# Rotary_Encoder.net
KiCad netlist of a schematic drawn in Altium Designer
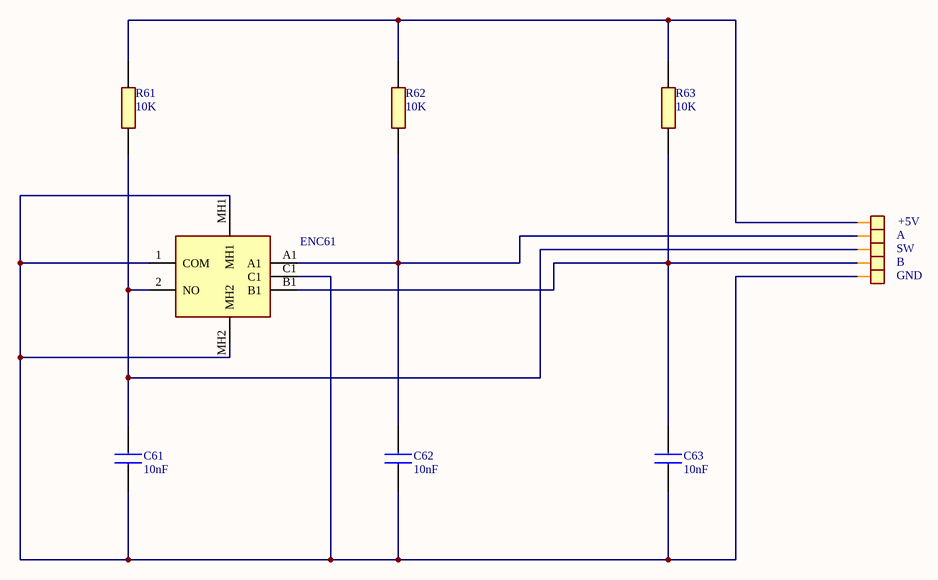
[diagram p0: Rotary_Encoder.SchDoc]

(export (version "E")
  (design (tool "Eeschema 10.0.6"))
  (components
    (comp (ref "C61")
      (value "10nF")
      (footprint "C315C103K5R5TA7303")
      (fields
        (field (name "MOUSER PART NUMBER") "80-C315C103K5R-TR")
        (field (name "MANUFACTURER_PART_NUMBER") "C315C103K5R5TA7303")
      )
      (libsource (lib "Master") (part "C315C103K5R5TA7303"))
    )
    (comp (ref "C62")
      (value "10nF")
      (footprint "C315C103K5R5TA7303")
      (fields
        (field (name "MOUSER PART NUMBER") "80-C315C103K5R-TR")
        (field (name "MANUFACTURER_PART_NUMBER") "C315C103K5R5TA7303")
      )
      (libsource (lib "Master") (part "C315C103K5R5TA7303"))
    )
    (comp (ref "C63")
      (value "10nF")
      (footprint "C315C103K5R5TA7303")
      (fields
        (field (name "MOUSER PART NUMBER") "80-C315C103K5R-TR")
        (field (name "MANUFACTURER_PART_NUMBER") "C315C103K5R5TA7303")
      )
      (libsource (lib "Master") (part "C315C103K5R5TA7303"))
    )
    (comp (ref "ENC61")
      (value "ROTARY&SWITCH")
      (footprint "Master:PEC11R4225FS0012")
      (description "Encoder 20mm SHAFT w/SWITCH")
      (fields
        (field (name "MANUFACTURER_PART_NUMBER") "PEC11R-4225F-S0012")
        (field (name "MOUSER PART NUMBER") "652-PEC11R-4225F-S12")
      )
      (libsource (lib "Master") (part "ROTARY"))
    )
    (comp (ref "H61") (value "+5V") (footprint "Header_M_S") (libsource (lib "Master") (part "Head_M_S")))
    (comp (ref "H62") (value "A") (footprint "Header_M_S") (libsource (lib "Master") (part "Head_M_S")))
    (comp (ref "H63") (value "SW") (footprint "Header_M_S") (libsource (lib "Master") (part "Head_M_S")))
    (comp (ref "H64") (value "B") (footprint "Header_M_S") (libsource (lib "Master") (part "Head_M_S")))
    (comp (ref "H65") (value "GND") (footprint "Header_M_S") (libsource (lib "Master") (part "Head_M_S")))
    (comp (ref "R61")
      (value "10K")
      (footprint "VISHAY_CMF_60")
      (description "Through Hole 1W 10/68 Kohms 1%")
      (fields
        (field (name "MANUFACTURER_PART_NUMBER") "CMF6010K000FKEB")
        (field (name "MOUSER PART NUMBER") "71-CMF6010K000FKEB")
      )
      (libsource (lib "Master") (part "RES_68K_10K"))
    )
    (comp (ref "R62")
      (value "10K")
      (footprint "VISHAY_CMF_60")
      (description "Through Hole 1W 10/68 Kohms 1%")
      (fields
        (field (name "MANUFACTURER_PART_NUMBER") "CMF6010K000FKEB")
        (field (name "MOUSER PART NUMBER") "71-CMF6010K000FKEB")
      )
      (libsource (lib "Master") (part "RES_68K_10K"))
    )
    (comp (ref "R63")
      (value "10K")
      (footprint "VISHAY_CMF_60")
      (description "Through Hole 1W 10/68 Kohms 1%")
      (fields
        (field (name "MANUFACTURER_PART_NUMBER") "CMF6010K000FKEB")
        (field (name "MOUSER PART NUMBER") "71-CMF6010K000FKEB")
      )
      (libsource (lib "Master") (part "RES_68K_10K"))
    )
  )
  (nets
    (net (code "1") (name "Net-(ENC61-COM)") (class "Default")
      (node (ref "C61") (pin "1") (pinfunction "1_1") (pintype "passive"))
      (node (ref "C62") (pin "1") (pinfunction "1_1") (pintype "passive"))
      (node (ref "C63") (pin "1") (pinfunction "1_1") (pintype "passive"))
      (node (ref "ENC61") (pin "1") (pinfunction "COM_1") (pintype "passive"))
      (node (ref "ENC61") (pin "C1") (pinfunction "C1_C1") (pintype "passive"))
      (node (ref "ENC61") (pin "MH1") (pinfunction "MH1_MH1") (pintype "passive"))
      (node (ref "ENC61") (pin "MH2") (pinfunction "MH2_MH2") (pintype "passive"))
      (node (ref "H65") (pin "H?") (pinfunction "HF_H?") (pintype "passive"))
    )
    (net (code "2") (name "Net-(ENC61-NO)") (class "Default")
      (node (ref "C61") (pin "2") (pinfunction "2_2") (pintype "passive"))
      (node (ref "ENC61") (pin "2") (pinfunction "NO_2") (pintype "passive"))
      (node (ref "H63") (pin "H?") (pinfunction "HF_H?") (pintype "passive"))
      (node (ref "R61") (pin "1") (pinfunction "1_1") (pintype "passive"))
    )
    (net (code "3") (name "Net-(H61-HF)") (class "Default")
      (node (ref "H61") (pin "H?") (pinfunction "HF_H?") (pintype "passive"))
      (node (ref "R61") (pin "2") (pinfunction "2_2") (pintype "passive"))
      (node (ref "R62") (pin "2") (pinfunction "2_2") (pintype "passive"))
      (node (ref "R63") (pin "2") (pinfunction "2_2") (pintype "passive"))
    )
    (net (code "4") (name "Net-(H62-HF)") (class "Default")
      (node (ref "C62") (pin "2") (pinfunction "2_2") (pintype "passive"))
      (node (ref "ENC61") (pin "A1") (pinfunction "A1_A1") (pintype "passive"))
      (node (ref "H62") (pin "H?") (pinfunction "HF_H?") (pintype "passive"))
      (node (ref "R62") (pin "1") (pinfunction "1_1") (pintype "passive"))
    )
    (net (code "5") (name "Net-(H64-HF)") (class "Default")
      (node (ref "C63") (pin "2") (pinfunction "2_2") (pintype "passive"))
      (node (ref "ENC61") (pin "B1") (pinfunction "B1_B1") (pintype "passive"))
      (node (ref "H64") (pin "H?") (pinfunction "HF_H?") (pintype "passive"))
      (node (ref "R63") (pin "1") (pinfunction "1_1") (pintype "passive"))
    )
  )
)
